# BrauV2_1Wire.net
KiCad netlist of a schematic drawn in Altium Designer
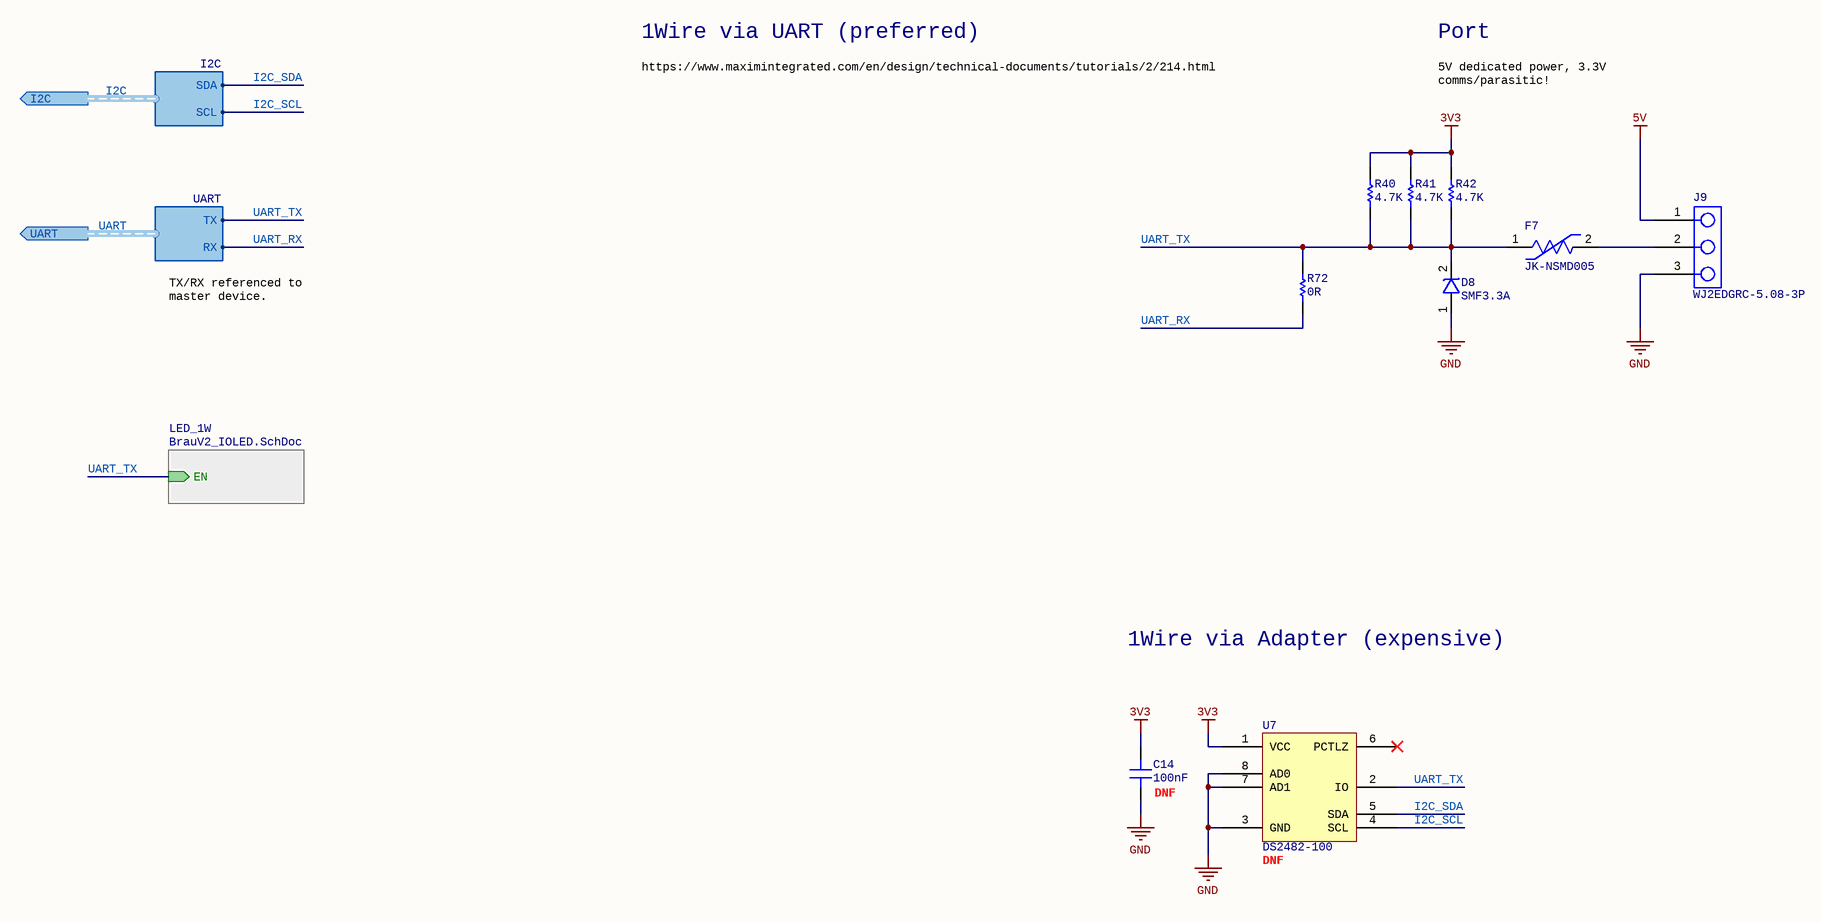
[diagram p0: BrauV2_1Wire.SchDoc]

(export (version "E")
  (design (tool "Eeschema 10.0.6"))
  (components
    (comp (ref "C14")
      (value "CC0402KRX5R6BB104")
      (footprint "SMD_CAP_0402(1005)_N")
      (description "100nF ±10% 10V X5R 0402 Multilayer Ceramic Capacitors MLCC - SMD/SMT RoHS")
      (fields (field (name "TOLERANCE") "10%") (field (name "CAPACITANCE") "100nF"))
      (libsource (lib "BrauV2_Capacitor") (part "100nF 0402 10V 10%"))
    )
    (comp (ref "D8")
      (value "SMF3.3A")
      (footprint "SOD-123FL")
      (description "Unidirectional 3.3V 5.2V 8V 25A SOD-123 TVS RoHS")
      (libsource (lib "BrauV2_Diode") (part "SMF3.3A"))
    )
    (comp (ref "F7")
      (value "JK-NSMD005")
      (footprint "SMD_RES_1206(3216)_N")
      (description "60V 150mA 1.5s 1206 PTC Resettable Fuses RoHS")
      (libsource (lib "BrauV2_Resistor") (part "JK-NSMD005"))
    )
    (comp (ref "J9")
      (value "WJ2EDGRC-5.08-3P")
      (footprint "796638-3")
      (description "Covered（4Sided） 3 1 0.200\"（5.08mm） 3 P=5.08mm Pluggable System Terminal Block RoHS")
      (libsource (lib "BrauV2_Connector") (part "WJ2EDGRC-5.08-3P"))
    )
    (comp (ref "R40")
      (value "RC0402FR-074K7L")
      (footprint "SMD_RES_0402(1005)_N")
      (description "4.7kΩ ±1% 1/16W ±100ppm/℃ 0402 Chip Resistor - Surface Mount RoHS")
      (fields (field (name "TOLERANCE") "1%") (field (name "RESISTANCE") "4.7K"))
      (libsource (lib "BrauV2_Resistor") (part "4K7 0402 1% 1/16W"))
    )
    (comp (ref "R41")
      (value "RC0402FR-074K7L")
      (footprint "SMD_RES_0402(1005)_N")
      (description "4.7kΩ ±1% 1/16W ±100ppm/℃ 0402 Chip Resistor - Surface Mount RoHS")
      (fields (field (name "TOLERANCE") "1%") (field (name "RESISTANCE") "4.7K"))
      (libsource (lib "BrauV2_Resistor") (part "4K7 0402 1% 1/16W"))
    )
    (comp (ref "R42")
      (value "RC0402FR-074K7L")
      (footprint "SMD_RES_0402(1005)_N")
      (description "4.7kΩ ±1% 1/16W ±100ppm/℃ 0402 Chip Resistor - Surface Mount RoHS")
      (fields (field (name "TOLERANCE") "1%") (field (name "RESISTANCE") "4.7K"))
      (libsource (lib "BrauV2_Resistor") (part "4K7 0402 1% 1/16W"))
    )
    (comp (ref "R72")
      (value "RC0402FR-070RL")
      (footprint "SMD_RES_0402(1005)_N")
      (description "0Ω ±1% 1/16W 0402 Chip Resistor - Surface Mount RoHS")
      (fields (field (name "TOLERANCE") "1%") (field (name "RESISTANCE") "0R"))
      (libsource (lib "BrauV2_Resistor") (part "0R 0402 1% 1/16W"))
    )
    (comp (ref "U7")
      (value "DS2482-100")
      (footprint "SOIC-8-3.9mm")
      (description "Single-Channel 1-Wire Master")
      (libsource (lib "BrauV2_IC") (part "DS2482-100"))
    )
  )
  (nets
    (net (code "3") (name "/I2C_SCL") (class "Default")
      (node (ref "U7") (pin "4") (pinfunction "SCL_4") (pintype "passive"))
    )
    (net (code "4") (name "/I2C_SDA") (class "Default")
      (node (ref "U7") (pin "5") (pinfunction "SDA_5") (pintype "passive"))
    )
    (net (code "6") (name "/UART_RX") (class "Default")
      (node (ref "R72") (pin "1") (pinfunction "1_1") (pintype "passive"))
    )
    (net (code "7") (name "/UART_TX") (class "Default")
      (node (ref "D8") (pin "2") (pinfunction "CATHODE_2") (pintype "passive"))
      (node (ref "F7") (pin "1") (pinfunction "1_1") (pintype "passive"))
      (node (ref "R40") (pin "1") (pinfunction "1_1") (pintype "passive"))
      (node (ref "R41") (pin "1") (pinfunction "1_1") (pintype "passive"))
      (node (ref "R42") (pin "1") (pinfunction "1_1") (pintype "passive"))
      (node (ref "R72") (pin "2") (pinfunction "2_2") (pintype "passive"))
      (node (ref "U7") (pin "2") (pinfunction "IO_2") (pintype "passive"))
    )
    (net (code "9") (name "3V3") (class "Default")
      (node (ref "C14") (pin "2") (pinfunction "2_2") (pintype "passive"))
      (node (ref "R40") (pin "2") (pinfunction "2_2") (pintype "passive"))
      (node (ref "R41") (pin "2") (pinfunction "2_2") (pintype "passive"))
      (node (ref "R42") (pin "2") (pinfunction "2_2") (pintype "passive"))
      (node (ref "U7") (pin "1") (pinfunction "VCC_1") (pintype "passive"))
    )
    (net (code "10") (name "5V") (class "Default")
      (node (ref "J9") (pin "1") (pinfunction "1_1") (pintype "passive"))
    )
    (net (code "11") (name "GND") (class "Default")
      (node (ref "C14") (pin "1") (pinfunction "1_1") (pintype "passive"))
      (node (ref "D8") (pin "1") (pinfunction "ANODE_1") (pintype "passive"))
      (node (ref "J9") (pin "3") (pinfunction "3_3") (pintype "passive"))
      (node (ref "U7") (pin "3") (pinfunction "GND_3") (pintype "passive"))
      (node (ref "U7") (pin "7") (pinfunction "AD1_7") (pintype "passive"))
      (node (ref "U7") (pin "8") (pinfunction "AD0_8") (pintype "passive"))
    )
    (net (code "12") (name "Net-(F7-Pad2)") (class "Default")
      (node (ref "F7") (pin "2") (pinfunction "2_2") (pintype "passive"))
      (node (ref "J9") (pin "2") (pinfunction "2_2") (pintype "passive"))
    )
    (net (code "13") (name "unconnected-(U7-PCTLZ-Pad6)") (class "Default")
      (node (ref "U7") (pin "6") (pinfunction "PCTLZ_6") (pintype "passive+no_connect"))
    )
  )
)
